# PET_AV_Interface.net
KiCad netlist of a schematic drawn in EAGLE
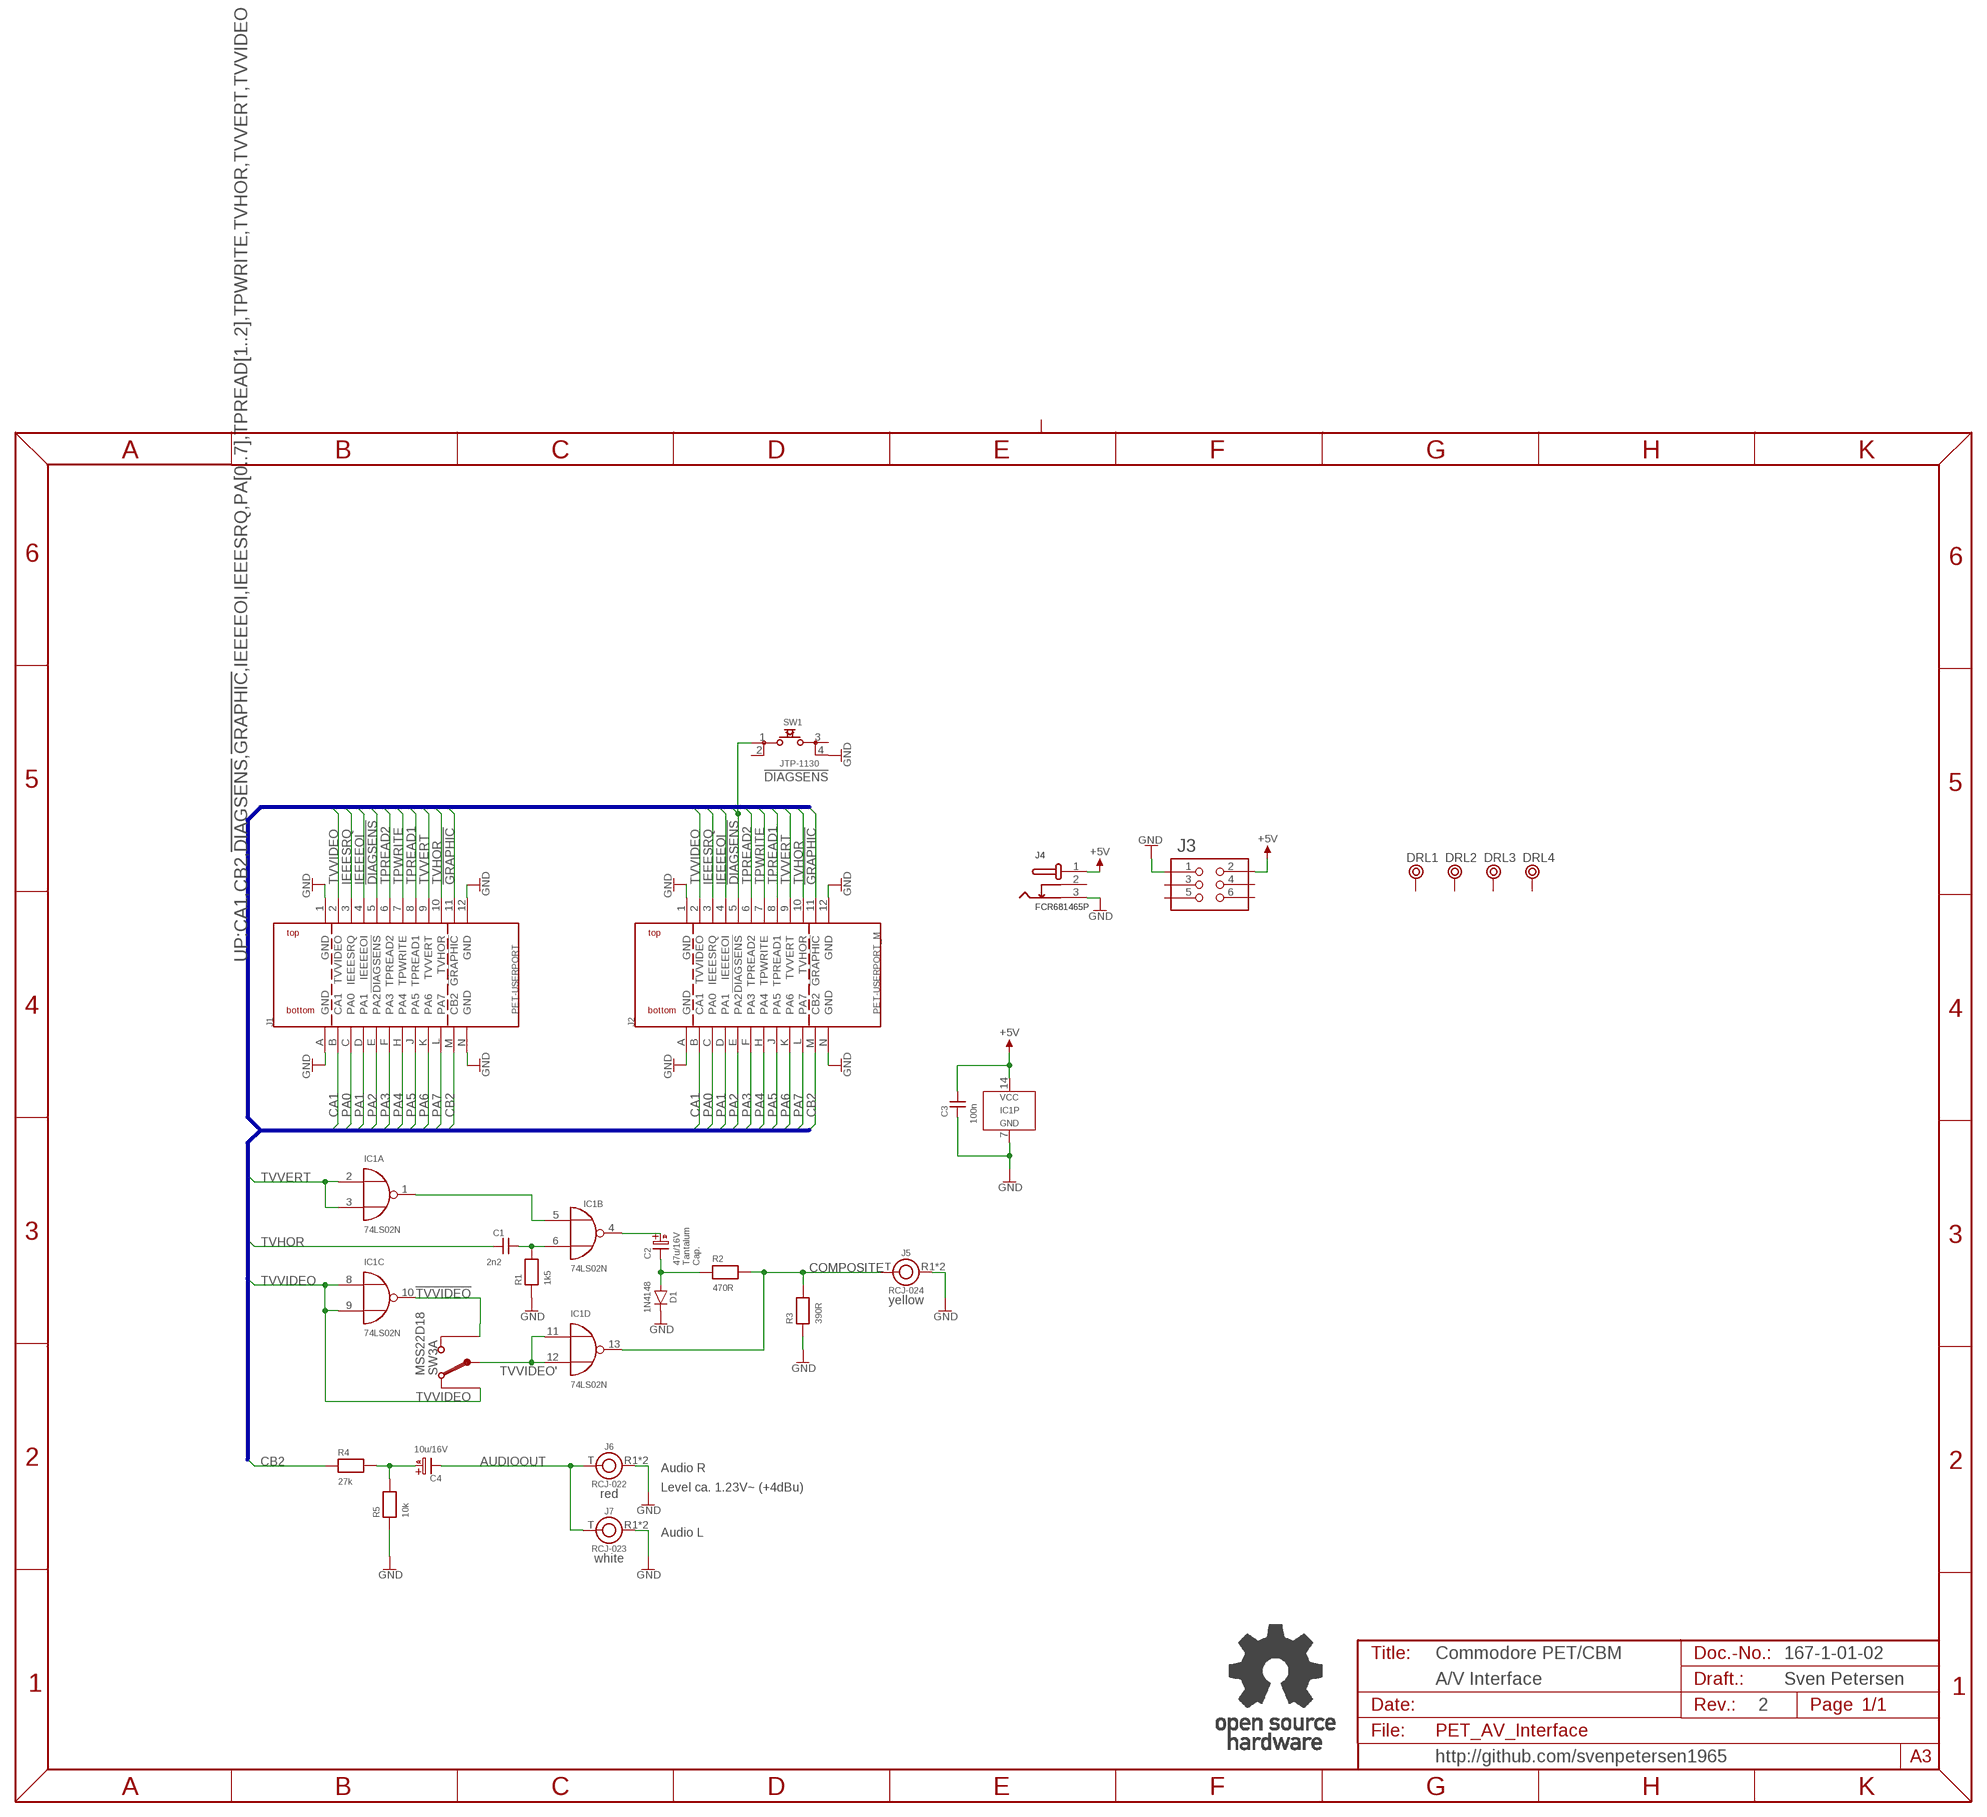
[diagram p0: schematic, sheet 1]

(export (version "E")
  (design (tool "Eeschema 10.0.6"))
  (components
    (comp (ref "C1")
      (value "2n2")
      (footprint "eagle-import:C-2,5")
      (libsource (lib "eagle-import") (part "CAP01"))
    )
    (comp (ref "C2")
      (value "47u/16V")
      (footprint "eagle-import:C5,0_2,0")
      (libsource (lib "eagle-import") (part "C05,0/2,0"))
    )
    (comp (ref "C3")
      (value "100n")
      (footprint "eagle-import:C-2,5")
      (libsource (lib "eagle-import") (part "CAP01"))
    )
    (comp (ref "C4")
      (value "10u/16V")
      (footprint "eagle-import:C5,0_2,0")
      (libsource (lib "eagle-import") (part "C05,0/2,0"))
    )
    (comp (ref "D1")
      (value "1N4148")
      (footprint "eagle-import:DO-35_3")
      (libsource (lib "eagle-import") (part "1N41480.3{dblquote}"))
    )
    (comp (ref "DRL1")
      (value "BOHR3,5")
      (footprint "eagle-import:BOHR3,5")
      (libsource (lib "eagle-import") (part "BOHR3,5"))
    )
    (comp (ref "DRL2")
      (value "BOHR3,5")
      (footprint "eagle-import:BOHR3,5")
      (libsource (lib "eagle-import") (part "BOHR3,5"))
    )
    (comp (ref "DRL3")
      (value "BOHR3,5")
      (footprint "eagle-import:BOHR3,5")
      (libsource (lib "eagle-import") (part "BOHR3,5"))
    )
    (comp (ref "DRL4")
      (value "BOHR3,5")
      (footprint "eagle-import:BOHR3,5")
      (libsource (lib "eagle-import") (part "BOHR3,5"))
    )
    (comp (ref "IC1")
      (value "74LS02N")
      (footprint "eagle-import:DIL-14")
      (libsource (lib "eagle-import") (part "7402N"))
    )
    (comp (ref "J1")
      (value "PET-USERPORT")
      (footprint "eagle-import:USERPORT")
      (libsource (lib "eagle-import") (part "PET-USERPORT"))
    )
    (comp (ref "J2")
      (value "PET-USERPORT_M")
      (footprint "eagle-import:USERPORT_M")
      (libsource (lib "eagle-import") (part "PET-USERPORT_M"))
    )
    (comp (ref "J3")
      (value "2X03WV")
      (footprint "eagle-import:2X03WV")
      (libsource (lib "eagle-import") (part "2X03WV"))
    )
    (comp (ref "J4")
      (value "FCR681465P")
      (footprint "eagle-import:FCR681465P")
      (libsource (lib "eagle-import") (part "FCR681465P"))
    )
    (comp (ref "J5")
      (value "RCJ-024")
      (footprint "eagle-import:RCJ-02X")
      (libsource (lib "eagle-import") (part "RCJ-02X"))
    )
    (comp (ref "J6")
      (value "RCJ-022")
      (footprint "eagle-import:RCJ-02X")
      (libsource (lib "eagle-import") (part "RCJ-02X"))
    )
    (comp (ref "J7")
      (value "RCJ-023")
      (footprint "eagle-import:RCJ-02X")
      (libsource (lib "eagle-import") (part "RCJ-02X"))
    )
    (comp (ref "R1")
      (value "1k5")
      (footprint "eagle-import:R-10")
      (libsource (lib "eagle-import") (part "RES04"))
    )
    (comp (ref "R2")
      (value "470R")
      (footprint "eagle-import:R-10")
      (libsource (lib "eagle-import") (part "RES04"))
    )
    (comp (ref "R3")
      (value "390R")
      (footprint "eagle-import:R-10")
      (libsource (lib "eagle-import") (part "RES04"))
    )
    (comp (ref "R4")
      (value "27k")
      (footprint "eagle-import:R-10")
      (libsource (lib "eagle-import") (part "RES04"))
    )
    (comp (ref "R5")
      (value "10k")
      (footprint "eagle-import:R-10")
      (libsource (lib "eagle-import") (part "RES04"))
    )
    (comp (ref "SW1")
      (value "JTP-1130")
      (footprint "eagle-import:JTP-1130")
      (libsource (lib "eagle-import") (part "JTP-1130"))
    )
    (comp (ref "SW3")
      (value "MSS22D18")
      (footprint "eagle-import:DPDT_9MM")
      (libsource (lib "eagle-import") (part "DPDT_9MM"))
    )
    (comp (ref "U$2")
      (value "OPEN_SOURCE_HW")
      (footprint "eagle-import:OPENHW")
      (libsource (lib "eagle-import") (part "OPEN_SOURCE_HW"))
    )
  )
  (nets
    (net (code "2") (name "+5V") (class "Default")
      (node (ref "C3") (pin "2") (pinfunction "2_2") (pintype "passive"))
      (node (ref "IC1") (pin "14") (pinfunction "VCC_14") (pintype "bidirectional"))
      (node (ref "J3") (pin "2") (pinfunction "2_2") (pintype "passive"))
      (node (ref "J4") (pin "1") (pinfunction "1_1") (pintype "bidirectional"))
    )
    (net (code "3") (name "/AUDIOOUT") (class "Default")
      (node (ref "C4") (pin "K") (pinfunction "-_K") (pintype "passive"))
      (node (ref "J6") (pin "T") (pinfunction "T_T") (pintype "bidirectional"))
      (node (ref "J7") (pin "T") (pinfunction "T_T") (pintype "bidirectional"))
    )
    (net (code "4") (name "/CA1") (class "Default")
      (node (ref "J1") (pin "B") (pinfunction "CA1_B") (pintype "input"))
      (node (ref "J2") (pin "B") (pinfunction "CA1_B") (pintype "input"))
    )
    (net (code "5") (name "/CB2") (class "Default")
      (node (ref "J1") (pin "M") (pinfunction "CB2_M") (pintype "bidirectional"))
      (node (ref "J2") (pin "M") (pinfunction "CB2_M") (pintype "bidirectional"))
      (node (ref "R4") (pin "1") (pinfunction "1_1") (pintype "passive"))
    )
    (net (code "6") (name "/COMPOSITE") (class "Default")
      (node (ref "IC1") (pin "13") (pinfunction "O_13") (pintype "output"))
      (node (ref "J5") (pin "T") (pinfunction "T_T") (pintype "bidirectional"))
      (node (ref "R2") (pin "2") (pinfunction "2_2") (pintype "passive"))
      (node (ref "R3") (pin "2") (pinfunction "2_2") (pintype "passive"))
    )
    (net (code "7") (name "/IEEEEOI") (class "Default")
      (node (ref "J1") (pin "4") (pinfunction "IEEEEOI_4") (pintype "output"))
      (node (ref "J2") (pin "4") (pinfunction "IEEEEOI_4") (pintype "output"))
    )
    (net (code "8") (name "/IEEESRQ") (class "Default")
      (node (ref "J1") (pin "3") (pinfunction "IEEESRQ_3") (pintype "output"))
      (node (ref "J2") (pin "3") (pinfunction "IEEESRQ_3") (pintype "output"))
    )
    (net (code "9") (name "/PA0") (class "Default")
      (node (ref "J1") (pin "C") (pinfunction "PA0_C") (pintype "bidirectional"))
      (node (ref "J2") (pin "C") (pinfunction "PA0_C") (pintype "bidirectional"))
    )
    (net (code "10") (name "/PA1") (class "Default")
      (node (ref "J1") (pin "D") (pinfunction "PA1_D") (pintype "bidirectional"))
      (node (ref "J2") (pin "D") (pinfunction "PA1_D") (pintype "bidirectional"))
    )
    (net (code "11") (name "/PA2") (class "Default")
      (node (ref "J1") (pin "E") (pinfunction "PA2_E") (pintype "bidirectional"))
      (node (ref "J2") (pin "E") (pinfunction "PA2_E") (pintype "bidirectional"))
    )
    (net (code "12") (name "/PA3") (class "Default")
      (node (ref "J1") (pin "F") (pinfunction "PA3_F") (pintype "bidirectional"))
      (node (ref "J2") (pin "F") (pinfunction "PA3_F") (pintype "bidirectional"))
    )
    (net (code "13") (name "/PA4") (class "Default")
      (node (ref "J1") (pin "H") (pinfunction "PA4_H") (pintype "bidirectional"))
      (node (ref "J2") (pin "H") (pinfunction "PA4_H") (pintype "bidirectional"))
    )
    (net (code "14") (name "/PA5") (class "Default")
      (node (ref "J1") (pin "J") (pinfunction "PA5_J") (pintype "bidirectional"))
      (node (ref "J2") (pin "J") (pinfunction "PA5_J") (pintype "bidirectional"))
    )
    (net (code "15") (name "/PA6") (class "Default")
      (node (ref "J1") (pin "K") (pinfunction "PA6_K") (pintype "bidirectional"))
      (node (ref "J2") (pin "K") (pinfunction "PA6_K") (pintype "bidirectional"))
    )
    (net (code "16") (name "/PA7") (class "Default")
      (node (ref "J1") (pin "L") (pinfunction "PA7_L") (pintype "bidirectional"))
      (node (ref "J2") (pin "L") (pinfunction "PA7_L") (pintype "bidirectional"))
    )
    (net (code "17") (name "/TPREAD1") (class "Default")
      (node (ref "J1") (pin "8") (pinfunction "TPREAD1_8") (pintype "output"))
      (node (ref "J2") (pin "8") (pinfunction "TPREAD1_8") (pintype "output"))
    )
    (net (code "18") (name "/TPREAD2") (class "Default")
      (node (ref "J1") (pin "6") (pinfunction "TPREAD2_6") (pintype "output"))
      (node (ref "J2") (pin "6") (pinfunction "TPREAD2_6") (pintype "output"))
    )
    (net (code "19") (name "/TPWRITE") (class "Default")
      (node (ref "J1") (pin "7") (pinfunction "TPWRITE_7") (pintype "output"))
      (node (ref "J2") (pin "7") (pinfunction "TPWRITE_7") (pintype "output"))
    )
    (net (code "20") (name "/TVHOR") (class "Default")
      (node (ref "C1") (pin "1") (pinfunction "1_1") (pintype "passive"))
      (node (ref "J1") (pin "10") (pinfunction "TVHOR_10") (pintype "output"))
      (node (ref "J2") (pin "10") (pinfunction "TVHOR_10") (pintype "output"))
    )
    (net (code "21") (name "/TVVERT") (class "Default")
      (node (ref "IC1") (pin "2") (pinfunction "I0_2") (pintype "input"))
      (node (ref "IC1") (pin "3") (pinfunction "I1_3") (pintype "input"))
      (node (ref "J1") (pin "9") (pinfunction "TVVERT_9") (pintype "output"))
      (node (ref "J2") (pin "9") (pinfunction "TVVERT_9") (pintype "output"))
    )
    (net (code "22") (name "/TVVIDEO") (class "Default")
      (node (ref "IC1") (pin "8") (pinfunction "I0_8") (pintype "input"))
      (node (ref "IC1") (pin "9") (pinfunction "I1_9") (pintype "input"))
      (node (ref "J1") (pin "2") (pinfunction "TVVIDEO_2") (pintype "output"))
      (node (ref "J2") (pin "2") (pinfunction "TVVIDEO_2") (pintype "output"))
      (node (ref "SW3") (pin "3") (pinfunction "DWN_3") (pintype "bidirectional"))
    )
    (net (code "23") (name "/TVVIDEO'") (class "Default")
      (node (ref "IC1") (pin "11") (pinfunction "I0_11") (pintype "input"))
      (node (ref "IC1") (pin "12") (pinfunction "I1_12") (pintype "input"))
      (node (ref "SW3") (pin "2") (pinfunction "COM_2") (pintype "bidirectional"))
    )
    (net (code "25") (name "/~{DIAGSENS}") (class "Default")
      (node (ref "J1") (pin "5") (pinfunction "~{DIAGSENS}_5") (pintype "output"))
      (node (ref "J2") (pin "5") (pinfunction "~{DIAGSENS}_5") (pintype "output"))
      (node (ref "SW1") (pin "1") (pinfunction "1_1") (pintype "passive"))
    )
    (net (code "26") (name "/~{GRAPHIC}") (class "Default")
      (node (ref "J1") (pin "11") (pinfunction "~{GRAPHIC}_11") (pintype "output"))
      (node (ref "J2") (pin "11") (pinfunction "~{GRAPHIC}_11") (pintype "output"))
    )
    (net (code "27") (name "/~{TVVIDEO}") (class "Default")
      (node (ref "IC1") (pin "10") (pinfunction "O_10") (pintype "output"))
      (node (ref "SW3") (pin "1") (pinfunction "UP_1") (pintype "bidirectional"))
    )
    (net (code "28") (name "GND") (class "Default")
      (node (ref "C3") (pin "1") (pinfunction "1_1") (pintype "passive"))
      (node (ref "D1") (pin "K") (pinfunction "K_K") (pintype "passive"))
      (node (ref "IC1") (pin "7") (pinfunction "GND_7") (pintype "bidirectional"))
      (node (ref "J1") (pin "1") (pinfunction "GND_1") (pintype "power_in"))
      (node (ref "J1") (pin "12") (pinfunction "GND_12") (pintype "power_in"))
      (node (ref "J1") (pin "A") (pinfunction "GND_A") (pintype "power_in"))
      (node (ref "J1") (pin "N") (pinfunction "GND_N") (pintype "power_in"))
      (node (ref "J2") (pin "1") (pinfunction "GND_1") (pintype "power_in"))
      (node (ref "J2") (pin "12") (pinfunction "GND_12") (pintype "power_in"))
      (node (ref "J2") (pin "A") (pinfunction "GND_A") (pintype "power_in"))
      (node (ref "J2") (pin "N") (pinfunction "GND_N") (pintype "power_in"))
      (node (ref "J3") (pin "1") (pinfunction "1_1") (pintype "passive"))
      (node (ref "J4") (pin "3") (pinfunction "3_3") (pintype "bidirectional"))
      (node (ref "J5") (pin "R1") (pinfunction "R_R1") (pintype "bidirectional"))
      (node (ref "J5") (pin "R2") (pinfunction "R_R2") (pintype "bidirectional"))
      (node (ref "J6") (pin "R1") (pinfunction "R_R1") (pintype "bidirectional"))
      (node (ref "J6") (pin "R2") (pinfunction "R_R2") (pintype "bidirectional"))
      (node (ref "J7") (pin "R1") (pinfunction "R_R1") (pintype "bidirectional"))
      (node (ref "J7") (pin "R2") (pinfunction "R_R2") (pintype "bidirectional"))
      (node (ref "R1") (pin "1") (pinfunction "1_1") (pintype "passive"))
      (node (ref "R3") (pin "1") (pinfunction "1_1") (pintype "passive"))
      (node (ref "R5") (pin "1") (pinfunction "1_1") (pintype "passive"))
      (node (ref "SW1") (pin "4") (pinfunction "4_4") (pintype "passive"))
    )
    (net (code "29") (name "Net-(C2-+)") (class "Default")
      (node (ref "C2") (pin "A") (pinfunction "+_A") (pintype "passive"))
      (node (ref "IC1") (pin "4") (pinfunction "O_4") (pintype "output"))
    )
    (net (code "30") (name "Net-(C2--)") (class "Default")
      (node (ref "C2") (pin "K") (pinfunction "-_K") (pintype "passive"))
      (node (ref "D1") (pin "A") (pinfunction "A_A") (pintype "passive"))
      (node (ref "R2") (pin "1") (pinfunction "1_1") (pintype "passive"))
    )
    (net (code "31") (name "Net-(C4-+)") (class "Default")
      (node (ref "C4") (pin "A") (pinfunction "+_A") (pintype "passive"))
      (node (ref "R4") (pin "2") (pinfunction "2_2") (pintype "passive"))
      (node (ref "R5") (pin "2") (pinfunction "2_2") (pintype "passive"))
    )
    (net (code "32") (name "Net-(IC1A-O)") (class "Default")
      (node (ref "IC1") (pin "1") (pinfunction "O_1") (pintype "output"))
      (node (ref "IC1") (pin "5") (pinfunction "I0_5") (pintype "input"))
    )
    (net (code "33") (name "Net-(IC1B-I1)") (class "Default")
      (node (ref "C1") (pin "2") (pinfunction "2_2") (pintype "passive"))
      (node (ref "IC1") (pin "6") (pinfunction "I1_6") (pintype "input"))
      (node (ref "R1") (pin "2") (pinfunction "2_2") (pintype "passive"))
    )
    (net (code "34") (name "unconnected-(DRL1-PadP$1)") (class "Default")
      (node (ref "DRL1") (pin "P$1") (pinfunction "P$1_P$1") (pintype "passive"))
    )
    (net (code "35") (name "unconnected-(DRL2-PadP$1)") (class "Default")
      (node (ref "DRL2") (pin "P$1") (pinfunction "P$1_P$1") (pintype "passive"))
    )
    (net (code "36") (name "unconnected-(DRL3-PadP$1)") (class "Default")
      (node (ref "DRL3") (pin "P$1") (pinfunction "P$1_P$1") (pintype "passive"))
    )
    (net (code "37") (name "unconnected-(DRL4-PadP$1)") (class "Default")
      (node (ref "DRL4") (pin "P$1") (pinfunction "P$1_P$1") (pintype "passive"))
    )
    (net (code "38") (name "unconnected-(J3-Pad3)") (class "Default")
      (node (ref "J3") (pin "3") (pinfunction "3_3") (pintype "passive"))
    )
    (net (code "39") (name "unconnected-(J3-Pad4)") (class "Default")
      (node (ref "J3") (pin "4") (pinfunction "4_4") (pintype "passive"))
    )
    (net (code "40") (name "unconnected-(J3-Pad5)") (class "Default")
      (node (ref "J3") (pin "5") (pinfunction "5_5") (pintype "passive"))
    )
    (net (code "41") (name "unconnected-(J3-Pad6)") (class "Default")
      (node (ref "J3") (pin "6") (pinfunction "6_6") (pintype "passive"))
    )
    (net (code "42") (name "unconnected-(J4-Pad2)") (class "Default")
      (node (ref "J4") (pin "2") (pinfunction "2_2") (pintype "bidirectional"))
    )
    (net (code "43") (name "unconnected-(SW1-Pad2)") (class "Default")
      (node (ref "SW1") (pin "2") (pinfunction "2_2") (pintype "passive"))
    )
    (net (code "44") (name "unconnected-(SW1-Pad3)") (class "Default")
      (node (ref "SW1") (pin "3") (pinfunction "3_3") (pintype "passive"))
    )
  )
)
